# Temp_sense.net
KiCad netlist of a schematic drawn in Altium Designer
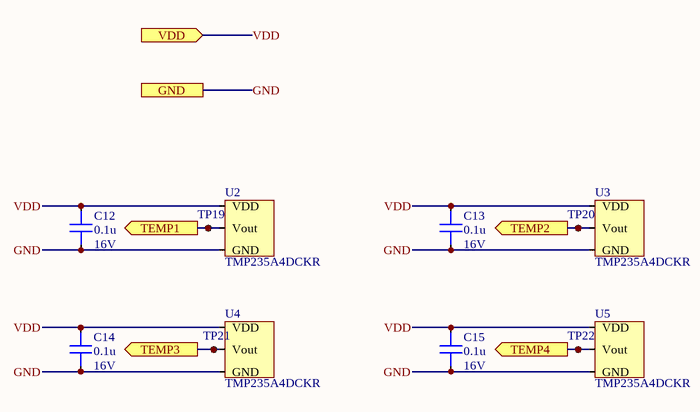
[diagram p0: Temp_sense.SchDoc]

(export (version "E")
  (design (tool "Eeschema 10.0.6"))
  (components
    (comp (ref "C12")
      (value "0.1u")
      (footprint "0603_CAP")
      (fields (field (name "VOLTAGE") "16V") (field (name "Comment") "Capacitor"))
      (libsource (lib "Capacitors") (part "Capacitor"))
    )
    (comp (ref "C13")
      (value "0.1u")
      (footprint "0603_CAP")
      (fields (field (name "VOLTAGE") "16V") (field (name "Comment") "Capacitor"))
      (libsource (lib "Capacitors") (part "Capacitor"))
    )
    (comp (ref "C14")
      (value "0.1u")
      (footprint "0603_CAP")
      (fields (field (name "VOLTAGE") "16V") (field (name "Comment") "Capacitor"))
      (libsource (lib "Capacitors") (part "Capacitor"))
    )
    (comp (ref "C15")
      (value "0.1u")
      (footprint "0603_CAP")
      (fields (field (name "VOLTAGE") "16V") (field (name "Comment") "Capacitor"))
      (libsource (lib "Capacitors") (part "Capacitor"))
    )
    (comp (ref "TP19")
      (value "1mm Testpoint")
      (footprint "1mm_testpoint")
      (description "1mm test point")
      (libsource (lib "Connectors") (part "1mm Testpoint"))
    )
    (comp (ref "TP20")
      (value "1mm Testpoint")
      (footprint "1mm_testpoint")
      (description "1mm test point")
      (libsource (lib "Connectors") (part "1mm Testpoint"))
    )
    (comp (ref "TP21")
      (value "1mm Testpoint")
      (footprint "1mm_testpoint")
      (description "1mm test point")
      (libsource (lib "Connectors") (part "1mm Testpoint"))
    )
    (comp (ref "TP22")
      (value "1mm Testpoint")
      (footprint "1mm_testpoint")
      (description "1mm test point")
      (libsource (lib "Connectors") (part "1mm Testpoint"))
    )
    (comp (ref "U2")
      (value "TMP235A4DCKR")
      (footprint "SOT23-3")
      (description "Temperature Sensor Analog, Local -40°C ~ 150°C 10mV/°C SOT-23-3")
      (libsource (lib "Analog_IC") (part "TMP235A4DCKR"))
    )
    (comp (ref "U3")
      (value "TMP235A4DCKR")
      (footprint "SOT23-3")
      (description "Temperature Sensor Analog, Local -40°C ~ 150°C 10mV/°C SOT-23-3")
      (libsource (lib "Analog_IC") (part "TMP235A4DCKR"))
    )
    (comp (ref "U4")
      (value "TMP235A4DCKR")
      (footprint "SOT23-3")
      (description "Temperature Sensor Analog, Local -40°C ~ 150°C 10mV/°C SOT-23-3")
      (libsource (lib "Analog_IC") (part "TMP235A4DCKR"))
    )
    (comp (ref "U5")
      (value "TMP235A4DCKR")
      (footprint "SOT23-3")
      (description "Temperature Sensor Analog, Local -40°C ~ 150°C 10mV/°C SOT-23-3")
      (libsource (lib "Analog_IC") (part "TMP235A4DCKR"))
    )
  )
  (nets
    (net (code "1") (name "/GND") (class "Default")
      (node (ref "C12") (pin "1") (pinfunction "1_1") (pintype "passive"))
      (node (ref "C13") (pin "1") (pinfunction "1_1") (pintype "passive"))
      (node (ref "C14") (pin "1") (pinfunction "1_1") (pintype "passive"))
      (node (ref "C15") (pin "1") (pinfunction "1_1") (pintype "passive"))
      (node (ref "U2") (pin "3") (pinfunction "GND_3") (pintype "passive"))
      (node (ref "U3") (pin "3") (pinfunction "GND_3") (pintype "passive"))
      (node (ref "U4") (pin "3") (pinfunction "GND_3") (pintype "passive"))
      (node (ref "U5") (pin "3") (pinfunction "GND_3") (pintype "passive"))
    )
    (net (code "2") (name "/TEMP1") (class "Default")
      (node (ref "TP19") (pin "1") (pintype "passive"))
      (node (ref "U2") (pin "2") (pinfunction "Vout_2") (pintype "passive"))
    )
    (net (code "3") (name "/TEMP2") (class "Default")
      (node (ref "TP20") (pin "1") (pintype "passive"))
      (node (ref "U3") (pin "2") (pinfunction "Vout_2") (pintype "passive"))
    )
    (net (code "4") (name "/TEMP3") (class "Default")
      (node (ref "TP21") (pin "1") (pintype "passive"))
      (node (ref "U4") (pin "2") (pinfunction "Vout_2") (pintype "passive"))
    )
    (net (code "5") (name "/TEMP4") (class "Default")
      (node (ref "TP22") (pin "1") (pintype "passive"))
      (node (ref "U5") (pin "2") (pinfunction "Vout_2") (pintype "passive"))
    )
    (net (code "6") (name "/VDD") (class "Default")
      (node (ref "C12") (pin "2") (pinfunction "2_2") (pintype "passive"))
      (node (ref "C13") (pin "2") (pinfunction "2_2") (pintype "passive"))
      (node (ref "C14") (pin "2") (pinfunction "2_2") (pintype "passive"))
      (node (ref "C15") (pin "2") (pinfunction "2_2") (pintype "passive"))
      (node (ref "U2") (pin "1") (pinfunction "VDD_1") (pintype "passive"))
      (node (ref "U3") (pin "1") (pinfunction "VDD_1") (pintype "passive"))
      (node (ref "U4") (pin "1") (pinfunction "VDD_1") (pintype "passive"))
      (node (ref "U5") (pin "1") (pinfunction "VDD_1") (pintype "passive"))
    )
  )
)
